# LCDTFT_CTRL_FT810.net
KiCad netlist of a schematic drawn in Altium Designer
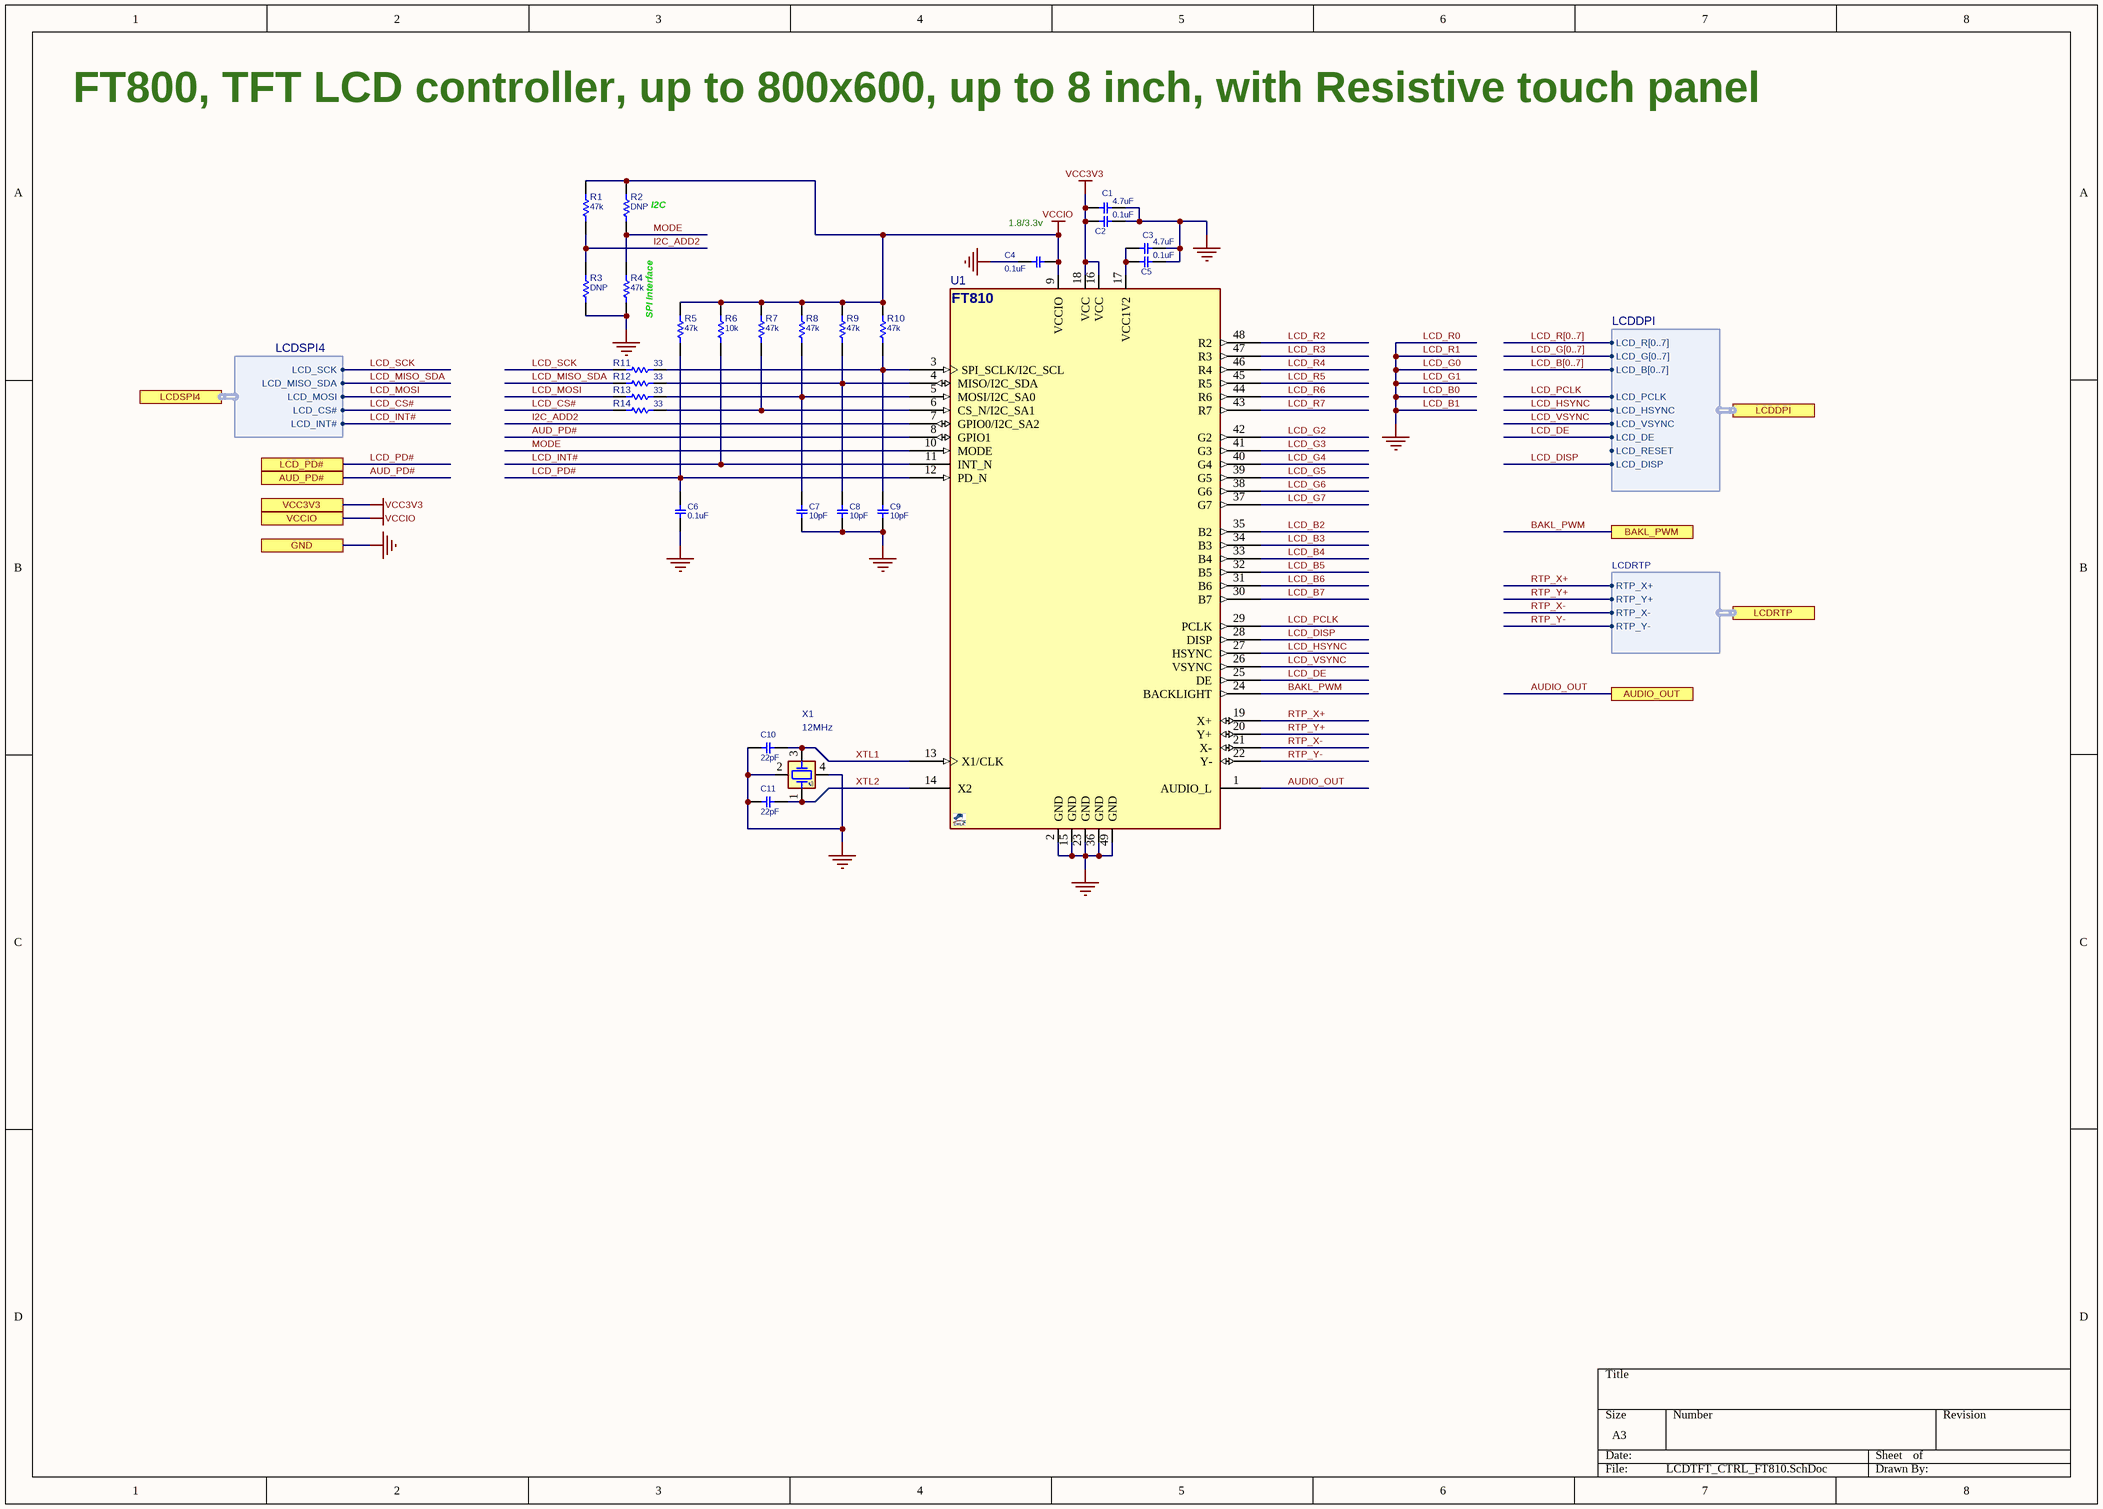
[diagram p0: LCDTFT_CTRL_FT810.SchDoc]

(export (version "E")
  (design (tool "Eeschema 10.0.6"))
  (components
    (comp (ref "C1")
      (value "4.7uF")
      (footprint "C0603")
      (description "CAP, MLCC")
      (libsource (lib "passive_smd") (part "CAP_SMD_MLCC"))
    )
    (comp (ref "C2")
      (value "0.1uF")
      (footprint "C0402")
      (description "CAP, MLCC")
      (fields (field (name "MANF_P#") "GRM155R71H104KE14D") (field (name "MANF") "Murata"))
      (libsource (lib "passive_smd") (part "CAP_SMD_MLCC"))
    )
    (comp (ref "C3")
      (value "4.7uF")
      (footprint "C0603")
      (description "CAP, MLCC")
      (libsource (lib "passive_smd") (part "CAP_SMD_MLCC"))
    )
    (comp (ref "C4")
      (value "0.1uF")
      (footprint "C0402")
      (description "CAP, MLCC")
      (fields (field (name "MANF_P#") "GRM155R71H104KE14D") (field (name "MANF") "Murata"))
      (libsource (lib "passive_smd") (part "CAP_SMD_MLCC"))
    )
    (comp (ref "C5")
      (value "0.1uF")
      (footprint "C0402")
      (description "CAP, MLCC")
      (fields (field (name "MANF_P#") "GRM155R71H104KE14D") (field (name "MANF") "Murata"))
      (libsource (lib "passive_smd") (part "CAP_SMD_MLCC"))
    )
    (comp (ref "C6")
      (value "0.1uF")
      (footprint "C0402")
      (description "CAP, MLCC")
      (fields (field (name "MANF_P#") "GRM155R71H104KE14D") (field (name "MANF") "Murata"))
      (libsource (lib "passive_smd") (part "CAP_SMD_MLCC"))
    )
    (comp (ref "C7")
      (value "10pF")
      (footprint "C0402")
      (description "CAP, MLCC")
      (libsource (lib "passive_smd") (part "CAP_SMD_MLCC"))
    )
    (comp (ref "C8")
      (value "10pF")
      (footprint "C0402")
      (description "CAP, MLCC")
      (libsource (lib "passive_smd") (part "CAP_SMD_MLCC"))
    )
    (comp (ref "C9")
      (value "10pF")
      (footprint "C0402")
      (description "CAP, MLCC")
      (libsource (lib "passive_smd") (part "CAP_SMD_MLCC"))
    )
    (comp (ref "C10")
      (value "22pF")
      (footprint "C0402")
      (description "CAP, MLCC")
      (libsource (lib "passive_smd") (part "CAP_SMD_MLCC"))
    )
    (comp (ref "C11")
      (value "22pF")
      (footprint "C0402")
      (description "CAP, MLCC")
      (libsource (lib "passive_smd") (part "CAP_SMD_MLCC"))
    )
    (comp (ref "R1")
      (value "47k")
      (footprint "R0402")
      (description "RESISTOR, SMD")
      (libsource (lib "passive_res_smd") (part "RES_SMD"))
    )
    (comp (ref "R2")
      (value "DNP")
      (footprint "R0402")
      (description "RESISTOR, SMD")
      (libsource (lib "passive_res_smd") (part "RES_SMD"))
    )
    (comp (ref "R3")
      (value "DNP")
      (footprint "R0402")
      (description "RESISTOR, SMD")
      (libsource (lib "passive_res_smd") (part "RES_SMD"))
    )
    (comp (ref "R4")
      (value "47k")
      (footprint "R0402")
      (description "RESISTOR, SMD")
      (libsource (lib "passive_res_smd") (part "RES_SMD"))
    )
    (comp (ref "R5")
      (value "47k")
      (footprint "R0402")
      (description "RESISTOR, SMD")
      (libsource (lib "passive_res_smd") (part "RES_SMD"))
    )
    (comp (ref "R6")
      (value "10k")
      (footprint "R0402")
      (description "RESISTOR, SMD")
      (libsource (lib "passive_res_smd") (part "RES_SMD"))
    )
    (comp (ref "R7")
      (value "47k")
      (footprint "R0402")
      (description "RESISTOR, SMD")
      (libsource (lib "passive_res_smd") (part "RES_SMD"))
    )
    (comp (ref "R8")
      (value "47k")
      (footprint "R0402")
      (description "RESISTOR, SMD")
      (libsource (lib "passive_res_smd") (part "RES_SMD"))
    )
    (comp (ref "R9")
      (value "47k")
      (footprint "R0402")
      (description "RESISTOR, SMD")
      (libsource (lib "passive_res_smd") (part "RES_SMD"))
    )
    (comp (ref "R10")
      (value "47k")
      (footprint "R0402")
      (description "RESISTOR, SMD")
      (libsource (lib "passive_res_smd") (part "RES_SMD"))
    )
    (comp (ref "R11")
      (value "33")
      (footprint "R0402")
      (description "RESISTOR, SMD")
      (libsource (lib "passive_res_smd") (part "RES_SMD"))
    )
    (comp (ref "R12")
      (value "33")
      (footprint "R0402")
      (description "RESISTOR, SMD")
      (libsource (lib "passive_res_smd") (part "RES_SMD"))
    )
    (comp (ref "R13")
      (value "33")
      (footprint "R0402")
      (description "RESISTOR, SMD")
      (libsource (lib "passive_res_smd") (part "RES_SMD"))
    )
    (comp (ref "R14")
      (value "33")
      (footprint "R0402")
      (description "RESISTOR, SMD")
      (libsource (lib "passive_res_smd") (part "RES_SMD"))
    )
    (comp (ref "U1")
      (value "FT810")
      (footprint "QFN50_48T")
      (description "LCD Display Controller, Embedded Video Engine, QFN-48")
      (fields (field (name "MANF") "FTDI/Bridgetek") (field (name "MANF_P#") "FT810Q"))
      (libsource (lib "lcdtft_controller") (part "FT810_QFN48"))
    )
    (comp (ref "X1")
      (value "12MHz")
      (footprint "XTL_4_3225")
      (description "Crystal 12MHz")
      (fields (field (name "MANF") "ECS") (field (name "MANF_P#") "ECS-120-18-33-JEM-TR"))
      (libsource (lib "crystal") (part "XTL_4_12MHz_3225"))
    )
  )
  (nets
    (net (code "4") (name "/AUDIO_OUT") (class "Default")
      (node (ref "U1") (pin "1") (pinfunction "AUDIO_L_1") (pintype "tri_state"))
    )
    (net (code "5") (name "/AUD_PD#") (class "Default")
      (node (ref "U1") (pin "8") (pinfunction "GPIO1_8") (pintype "bidirectional"))
    )
    (net (code "6") (name "/BAKL_PWM") (class "Default")
      (node (ref "U1") (pin "24") (pinfunction "BACKLIGHT_24") (pintype "output"))
    )
    (net (code "7") (name "/I2C_ADD2") (class "Default")
      (node (ref "R1") (pin "2") (pinfunction "2_2") (pintype "passive"))
      (node (ref "R3") (pin "1") (pinfunction "1_1") (pintype "passive"))
      (node (ref "U1") (pin "7") (pinfunction "GPIO0/I2C_SA2_7") (pintype "bidirectional"))
    )
    (net (code "9") (name "/LCD_B2") (class "Default")
      (node (ref "U1") (pin "35") (pinfunction "B2_35") (pintype "output"))
    )
    (net (code "10") (name "/LCD_B3") (class "Default")
      (node (ref "U1") (pin "34") (pinfunction "B3_34") (pintype "output"))
    )
    (net (code "11") (name "/LCD_B4") (class "Default")
      (node (ref "U1") (pin "33") (pinfunction "B4_33") (pintype "output"))
    )
    (net (code "12") (name "/LCD_B5") (class "Default")
      (node (ref "U1") (pin "32") (pinfunction "B5_32") (pintype "output"))
    )
    (net (code "13") (name "/LCD_B6") (class "Default")
      (node (ref "U1") (pin "31") (pinfunction "B6_31") (pintype "output"))
    )
    (net (code "14") (name "/LCD_B7") (class "Default")
      (node (ref "U1") (pin "30") (pinfunction "B7_30") (pintype "output"))
    )
    (net (code "16") (name "/LCD_CS#") (class "Default")
      (node (ref "R14") (pin "1") (pinfunction "1_1") (pintype "passive"))
    )
    (net (code "17") (name "/LCD_DE") (class "Default")
      (node (ref "U1") (pin "25") (pinfunction "DE_25") (pintype "output"))
    )
    (net (code "18") (name "/LCD_DISP") (class "Default")
      (node (ref "U1") (pin "28") (pinfunction "DISP_28") (pintype "output"))
    )
    (net (code "19") (name "/LCD_G2") (class "Default")
      (node (ref "U1") (pin "42") (pinfunction "G2_42") (pintype "output"))
    )
    (net (code "20") (name "/LCD_G3") (class "Default")
      (node (ref "U1") (pin "41") (pinfunction "G3_41") (pintype "output"))
    )
    (net (code "21") (name "/LCD_G4") (class "Default")
      (node (ref "U1") (pin "40") (pinfunction "G4_40") (pintype "output"))
    )
    (net (code "22") (name "/LCD_G5") (class "Default")
      (node (ref "U1") (pin "39") (pinfunction "G5_39") (pintype "output"))
    )
    (net (code "23") (name "/LCD_G6") (class "Default")
      (node (ref "U1") (pin "38") (pinfunction "G6_38") (pintype "output"))
    )
    (net (code "24") (name "/LCD_G7") (class "Default")
      (node (ref "U1") (pin "37") (pinfunction "G7_37") (pintype "output"))
    )
    (net (code "26") (name "/LCD_HSYNC") (class "Default")
      (node (ref "U1") (pin "27") (pinfunction "HSYNC_27") (pintype "output"))
    )
    (net (code "27") (name "/LCD_INT#") (class "Default")
      (node (ref "R6") (pin "2") (pinfunction "2_2") (pintype "passive"))
      (node (ref "U1") (pin "11") (pinfunction "INT_N_11") (pintype "tri_state"))
    )
    (net (code "28") (name "/LCD_MISO_SDA") (class "Default")
      (node (ref "R12") (pin "1") (pinfunction "1_1") (pintype "passive"))
    )
    (net (code "29") (name "/LCD_MOSI") (class "Default")
      (node (ref "R13") (pin "1") (pinfunction "1_1") (pintype "passive"))
    )
    (net (code "30") (name "/LCD_PCLK") (class "Default")
      (node (ref "U1") (pin "29") (pinfunction "PCLK_29") (pintype "output"))
    )
    (net (code "31") (name "/LCD_PD#") (class "Default")
      (node (ref "C6") (pin "1") (pinfunction "1_1") (pintype "passive"))
      (node (ref "R5") (pin "2") (pinfunction "2_2") (pintype "passive"))
      (node (ref "U1") (pin "12") (pinfunction "PD_N_12") (pintype "input"))
    )
    (net (code "32") (name "/LCD_R2") (class "Default")
      (node (ref "U1") (pin "48") (pinfunction "R2_48") (pintype "output"))
    )
    (net (code "33") (name "/LCD_R3") (class "Default")
      (node (ref "U1") (pin "47") (pinfunction "R3_47") (pintype "output"))
    )
    (net (code "34") (name "/LCD_R4") (class "Default")
      (node (ref "U1") (pin "46") (pinfunction "R4_46") (pintype "output"))
    )
    (net (code "35") (name "/LCD_R5") (class "Default")
      (node (ref "U1") (pin "45") (pinfunction "R5_45") (pintype "output"))
    )
    (net (code "36") (name "/LCD_R6") (class "Default")
      (node (ref "U1") (pin "44") (pinfunction "R6_44") (pintype "output"))
    )
    (net (code "37") (name "/LCD_R7") (class "Default")
      (node (ref "U1") (pin "43") (pinfunction "R7_43") (pintype "output"))
    )
    (net (code "38") (name "/LCD_SCK") (class "Default")
      (node (ref "R11") (pin "1") (pinfunction "1_1") (pintype "passive"))
    )
    (net (code "39") (name "/LCD_VSYNC") (class "Default")
      (node (ref "U1") (pin "26") (pinfunction "VSYNC_26") (pintype "output"))
    )
    (net (code "40") (name "/MODE") (class "Default")
      (node (ref "R2") (pin "2") (pinfunction "2_2") (pintype "passive"))
      (node (ref "R4") (pin "1") (pinfunction "1_1") (pintype "passive"))
      (node (ref "U1") (pin "10") (pinfunction "MODE_10") (pintype "input"))
    )
    (net (code "41") (name "/RTP_X+") (class "Default")
      (node (ref "U1") (pin "19") (pinfunction "X+_19") (pintype "bidirectional"))
    )
    (net (code "42") (name "/RTP_X-") (class "Default")
      (node (ref "U1") (pin "21") (pinfunction "X-_21") (pintype "bidirectional"))
    )
    (net (code "43") (name "/RTP_Y+") (class "Default")
      (node (ref "U1") (pin "20") (pinfunction "Y+_20") (pintype "bidirectional"))
    )
    (net (code "44") (name "/RTP_Y-") (class "Default")
      (node (ref "U1") (pin "22") (pinfunction "Y-_22") (pintype "bidirectional"))
    )
    (net (code "45") (name "/XTL1") (class "Default")
      (node (ref "C10") (pin "2") (pinfunction "2_2") (pintype "passive"))
      (node (ref "U1") (pin "13") (pinfunction "X1/CLK_13") (pintype "input"))
      (node (ref "X1") (pin "3") (pinfunction "2_3") (pintype "passive"))
    )
    (net (code "46") (name "/XTL2") (class "Default")
      (node (ref "C11") (pin "1") (pinfunction "1_1") (pintype "passive"))
      (node (ref "U1") (pin "14") (pinfunction "X2_14") (pintype "passive"))
      (node (ref "X1") (pin "1") (pinfunction "1_1") (pintype "passive"))
    )
    (net (code "50") (name "GND") (class "Default")
      (node (ref "C1") (pin "1") (pinfunction "1_1") (pintype "passive"))
      (node (ref "C10") (pin "1") (pinfunction "1_1") (pintype "passive"))
      (node (ref "C11") (pin "2") (pinfunction "2_2") (pintype "passive"))
      (node (ref "C2") (pin "1") (pinfunction "1_1") (pintype "passive"))
      (node (ref "C3") (pin "1") (pinfunction "1_1") (pintype "passive"))
      (node (ref "C4") (pin "2") (pinfunction "2_2") (pintype "passive"))
      (node (ref "C5") (pin "1") (pinfunction "1_1") (pintype "passive"))
      (node (ref "C6") (pin "2") (pinfunction "2_2") (pintype "passive"))
      (node (ref "C7") (pin "2") (pinfunction "2_2") (pintype "passive"))
      (node (ref "C8") (pin "2") (pinfunction "2_2") (pintype "passive"))
      (node (ref "C9") (pin "2") (pinfunction "2_2") (pintype "passive"))
      (node (ref "R3") (pin "2") (pinfunction "2_2") (pintype "passive"))
      (node (ref "R4") (pin "2") (pinfunction "2_2") (pintype "passive"))
      (node (ref "U1") (pin "15") (pinfunction "GND_15") (pintype "power_in"))
      (node (ref "U1") (pin "2") (pinfunction "GND_2") (pintype "power_in"))
      (node (ref "U1") (pin "23") (pinfunction "GND_23") (pintype "power_in"))
      (node (ref "U1") (pin "36") (pinfunction "GND_36") (pintype "power_in"))
      (node (ref "U1") (pin "49") (pinfunction "GND_49") (pintype "power_in"))
      (node (ref "X1") (pin "2") (pinfunction "2_2") (pintype "passive"))
      (node (ref "X1") (pin "4") (pinfunction "4_4") (pintype "passive"))
    )
    (net (code "51") (name "Net-(U1-CS_N{slash}I2C_SA1)") (class "Default")
      (node (ref "R14") (pin "2") (pinfunction "2_2") (pintype "passive"))
      (node (ref "R7") (pin "2") (pinfunction "2_2") (pintype "passive"))
      (node (ref "U1") (pin "6") (pinfunction "CS_N/I2C_SA1_6") (pintype "input"))
    )
    (net (code "52") (name "Net-(U1-MISO{slash}I2C_SDA)") (class "Default")
      (node (ref "C8") (pin "1") (pinfunction "1_1") (pintype "passive"))
      (node (ref "R12") (pin "2") (pinfunction "2_2") (pintype "passive"))
      (node (ref "R9") (pin "2") (pinfunction "2_2") (pintype "passive"))
      (node (ref "U1") (pin "4") (pinfunction "MISO/I2C_SDA_4") (pintype "bidirectional"))
    )
    (net (code "53") (name "Net-(U1-MOSI{slash}I2C_SA0)") (class "Default")
      (node (ref "C7") (pin "1") (pinfunction "1_1") (pintype "passive"))
      (node (ref "R13") (pin "2") (pinfunction "2_2") (pintype "passive"))
      (node (ref "R8") (pin "2") (pinfunction "2_2") (pintype "passive"))
      (node (ref "U1") (pin "5") (pinfunction "MOSI/I2C_SA0_5") (pintype "input"))
    )
    (net (code "54") (name "Net-(U1-SPI_SCLK{slash}I2C_SCL)") (class "Default")
      (node (ref "C9") (pin "1") (pinfunction "1_1") (pintype "passive"))
      (node (ref "R10") (pin "2") (pinfunction "2_2") (pintype "passive"))
      (node (ref "R11") (pin "2") (pinfunction "2_2") (pintype "passive"))
      (node (ref "U1") (pin "3") (pinfunction "SPI_SCLK/I2C_SCL_3") (pintype "input"))
    )
    (net (code "55") (name "Net-(U1-VCC1V2)") (class "Default")
      (node (ref "C3") (pin "2") (pinfunction "2_2") (pintype "passive"))
      (node (ref "C5") (pin "2") (pinfunction "2_2") (pintype "passive"))
      (node (ref "U1") (pin "17") (pinfunction "VCC1V2_17") (pintype "power_in"))
    )
    (net (code "56") (name "VCC3V3") (class "Default")
      (node (ref "C1") (pin "2") (pinfunction "2_2") (pintype "passive"))
      (node (ref "C2") (pin "2") (pinfunction "2_2") (pintype "passive"))
      (node (ref "U1") (pin "16") (pinfunction "VCC_16") (pintype "power_in"))
      (node (ref "U1") (pin "18") (pinfunction "VCC_18") (pintype "power_in"))
    )
    (net (code "57") (name "VCCIO") (class "Default")
      (node (ref "C4") (pin "1") (pinfunction "1_1") (pintype "passive"))
      (node (ref "R1") (pin "1") (pinfunction "1_1") (pintype "passive"))
      (node (ref "R10") (pin "1") (pinfunction "1_1") (pintype "passive"))
      (node (ref "R2") (pin "1") (pinfunction "1_1") (pintype "passive"))
      (node (ref "R5") (pin "1") (pinfunction "1_1") (pintype "passive"))
      (node (ref "R6") (pin "1") (pinfunction "1_1") (pintype "passive"))
      (node (ref "R7") (pin "1") (pinfunction "1_1") (pintype "passive"))
      (node (ref "R8") (pin "1") (pinfunction "1_1") (pintype "passive"))
      (node (ref "R9") (pin "1") (pinfunction "1_1") (pintype "passive"))
      (node (ref "U1") (pin "9") (pinfunction "VCCIO_9") (pintype "power_in"))
    )
  )
)
